# Compute_Module_EXT_INTERFACES.net
KiCad netlist of a schematic drawn in Altium Designer
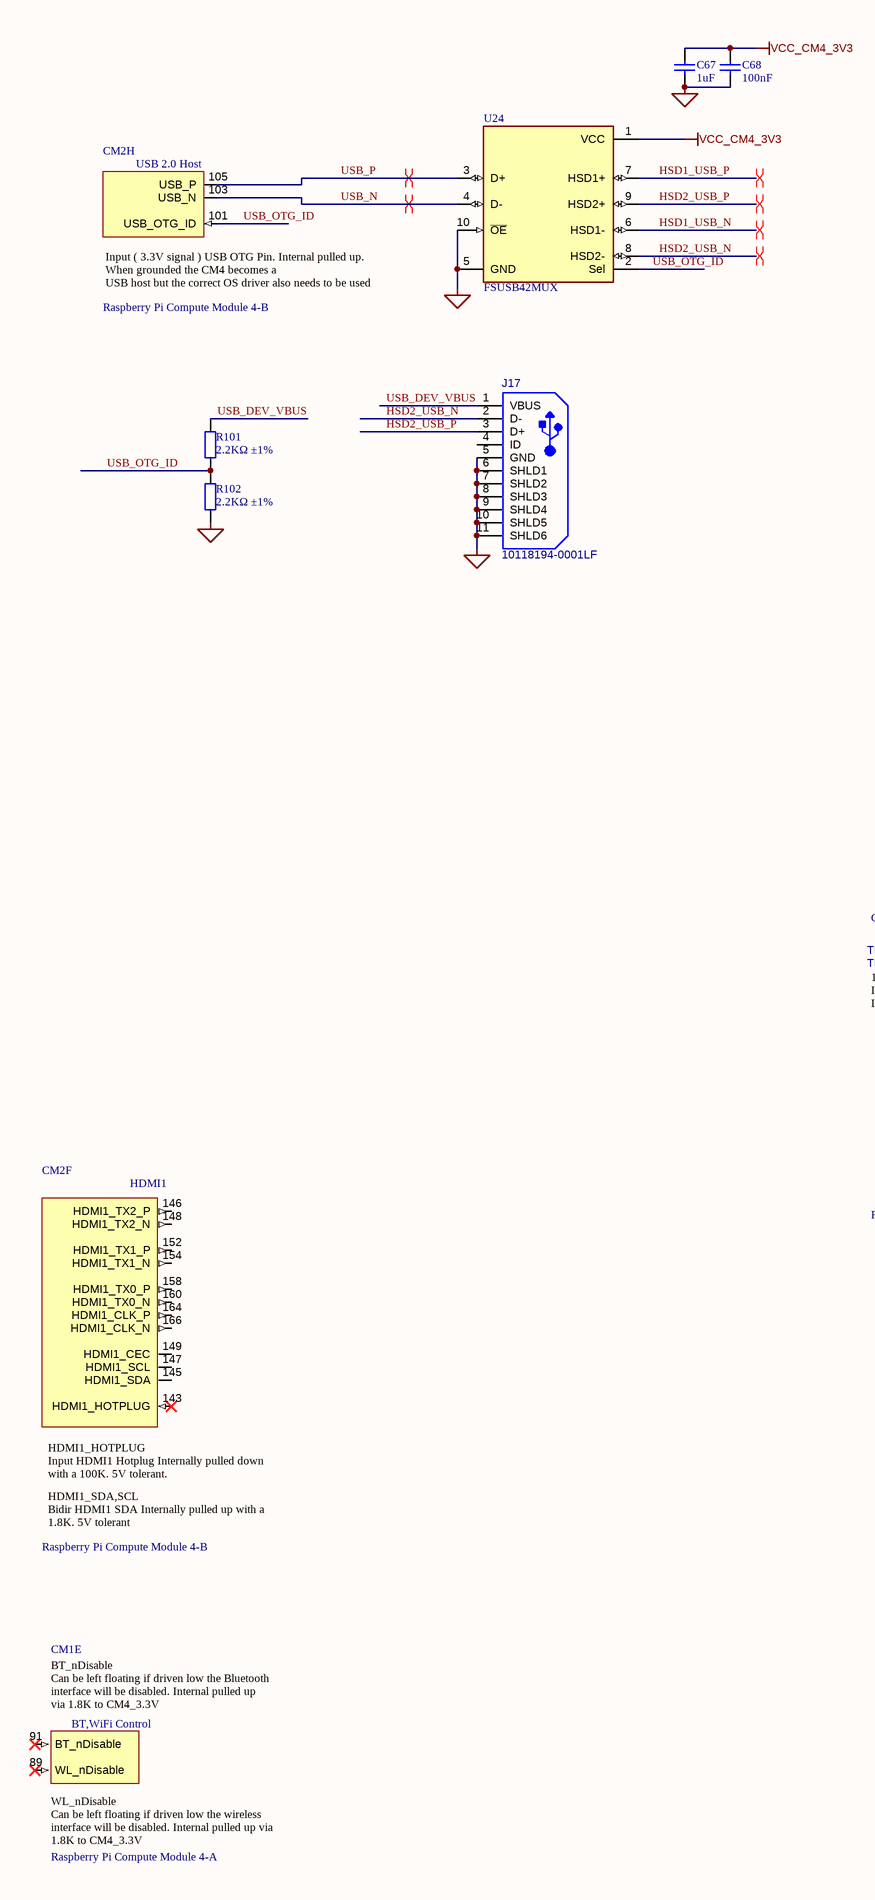
[diagram p0: Compute_Module_EXT_INTERFACES.SchDoc, left]
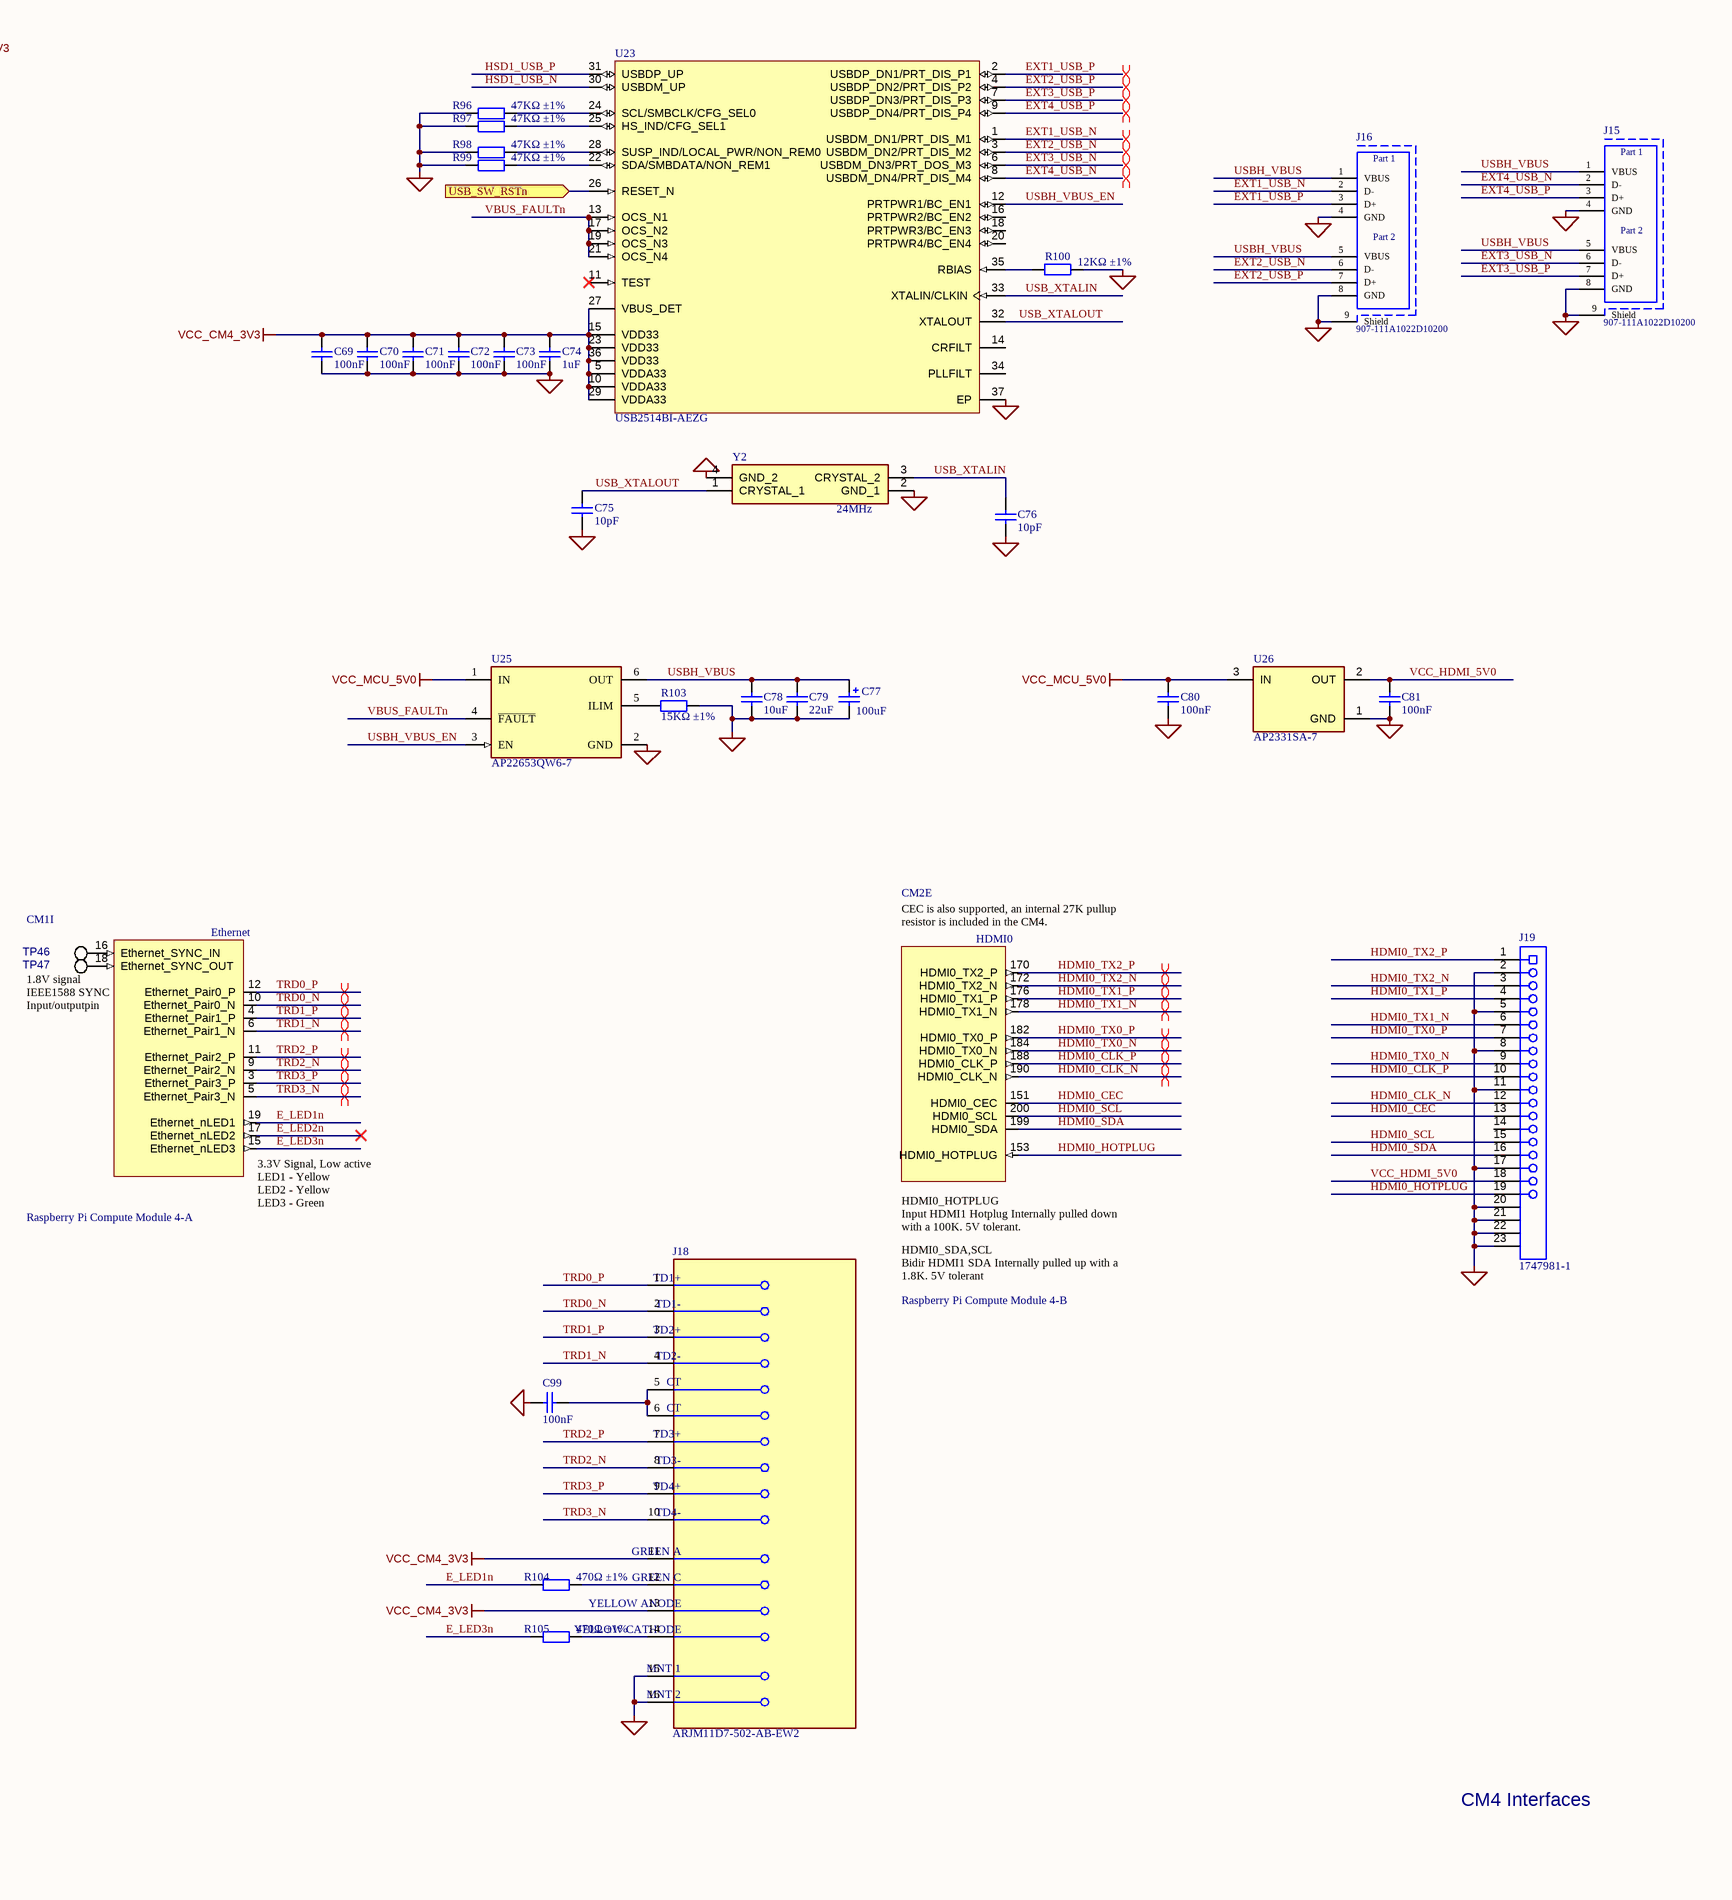
[diagram p1: Compute_Module_EXT_INTERFACES.SchDoc, right]

(export (version "E")
  (design (tool "Eeschema 10.0.6"))
  (components
    (comp (ref "C67")
      (value "1uF")
      (footprint "0603_C")
      (description "Chip capacitors")
      (fields
        (field (name "MANUFACTURER") "Samsung Electro-Mechanics")
        (field (name "MANUFACTURER PART NUMBER") "CL10A105KB8NNNC")
      )
      (libsource (lib "Cap") (part "0603 1uF (105) 10% 50V"))
    )
    (comp (ref "C68")
      (value "100nF")
      (footprint "0603_C")
      (description "Chip capacitors")
      (fields
        (field (name "MANUFACTURER") "YAGEO")
        (field (name "MANUFACTURER PART NUMBER") "CC0603KRX7R9BB104")
      )
      (libsource (lib "Cap") (part "0603 100nF (104) 10% 50V"))
    )
    (comp (ref "C69")
      (value "100nF")
      (footprint "0603_C")
      (description "Chip capacitors")
      (fields
        (field (name "MANUFACTURER") "YAGEO")
        (field (name "MANUFACTURER PART NUMBER") "CC0603KRX7R9BB104")
      )
      (libsource (lib "Cap") (part "0603 100nF (104) 10% 50V"))
    )
    (comp (ref "C70")
      (value "100nF")
      (footprint "0603_C")
      (description "Chip capacitors")
      (fields
        (field (name "MANUFACTURER") "YAGEO")
        (field (name "MANUFACTURER PART NUMBER") "CC0603KRX7R9BB104")
      )
      (libsource (lib "Cap") (part "0603 100nF (104) 10% 50V"))
    )
    (comp (ref "C71")
      (value "100nF")
      (footprint "0603_C")
      (description "Chip capacitors")
      (fields
        (field (name "MANUFACTURER") "YAGEO")
        (field (name "MANUFACTURER PART NUMBER") "CC0603KRX7R9BB104")
      )
      (libsource (lib "Cap") (part "0603 100nF (104) 10% 50V"))
    )
    (comp (ref "C72")
      (value "100nF")
      (footprint "0603_C")
      (description "Chip capacitors")
      (fields
        (field (name "MANUFACTURER") "YAGEO")
        (field (name "MANUFACTURER PART NUMBER") "CC0603KRX7R9BB104")
      )
      (libsource (lib "Cap") (part "0603 100nF (104) 10% 50V"))
    )
    (comp (ref "C73")
      (value "100nF")
      (footprint "0603_C")
      (description "Chip capacitors")
      (fields
        (field (name "MANUFACTURER") "YAGEO")
        (field (name "MANUFACTURER PART NUMBER") "CC0603KRX7R9BB104")
      )
      (libsource (lib "Cap") (part "0603 100nF (104) 10% 50V"))
    )
    (comp (ref "C74")
      (value "1uF")
      (footprint "0603_C")
      (description "Chip capacitors")
      (fields
        (field (name "MANUFACTURER") "Samsung Electro-Mechanics")
        (field (name "MANUFACTURER PART NUMBER") "CL10A105KB8NNNC")
      )
      (libsource (lib "Cap") (part "0603 1uF (105) 10% 50V"))
    )
    (comp (ref "C75")
      (value "10pF")
      (footprint "0603_C")
      (description "Chip capacitors")
      (fields
        (field (name "MANUFACTURER") "Samsung Electro-Mechanics")
        (field (name "PARTNUMBER") "CL10C100JB8NNNC")
      )
      (libsource (lib "Cap") (part "0603 10pF (100) 5% 50V"))
    )
    (comp (ref "C76")
      (value "10pF")
      (footprint "0603_C")
      (description "Chip capacitors")
      (fields
        (field (name "MANUFACTURER") "Samsung Electro-Mechanics")
        (field (name "PARTNUMBER") "CL10C100JB8NNNC")
      )
      (libsource (lib "Cap") (part "0603 10pF (100) 5% 50V"))
    )
    (comp (ref "C77")
      (value "100uF")
      (footprint "WCAP-ASLI_D6.3H7.7")
      (fields
        (field (name "MANUFACTURER") "Capxon International Elec")
        (field (name "MANUFACTURER PART NUMBER") "HV101M035E077ETR")
      )
      (libsource (lib "IQAnalog") (part "865080445010"))
    )
    (comp (ref "C78")
      (value "10uF")
      (footprint "1206_C")
      (description "Chip capacitors")
      (fields
        (field (name "MANUFACTURER") "Samsung Electro-Mechanics")
        (field (name "MANUFACTURER PART NUMBER") "CL31A106KBHNNNE")
      )
      (libsource (lib "Cap") (part "1206 10uF (106) 10% 50V"))
    )
    (comp (ref "C79")
      (value "22uF")
      (footprint "0805_C")
      (description "Chip capacitors")
      (fields
        (field (name "MANUFACTURER") "Samsung Electro-Mechanics")
        (field (name "PARTNUMBER") "CL21A226MAQNNNE")
      )
      (libsource (lib "Cap") (part "0805 22uF (226) 20% 25V"))
    )
    (comp (ref "C80")
      (value "100nF")
      (footprint "0603_C")
      (description "Chip capacitors")
      (fields
        (field (name "MANUFACTURER") "YAGEO")
        (field (name "MANUFACTURER PART NUMBER") "CC0603KRX7R9BB104")
      )
      (libsource (lib "Cap") (part "0603 100nF (104) 10% 50V"))
    )
    (comp (ref "C81")
      (value "100nF")
      (footprint "0603_C")
      (description "Chip capacitors")
      (fields
        (field (name "MANUFACTURER") "YAGEO")
        (field (name "MANUFACTURER PART NUMBER") "CC0603KRX7R9BB104")
      )
      (libsource (lib "Cap") (part "0603 100nF (104) 10% 50V"))
    )
    (comp (ref "C99")
      (value "100nF")
      (footprint "0603_C")
      (description "Chip capacitors")
      (fields
        (field (name "MANUFACTURER") "YAGEO")
        (field (name "MANUFACTURER PART NUMBER") "CC0603KRX7R9BB104")
      )
      (libsource (lib "Cap") (part "0603 100nF (104) 10% 50V"))
    )
    (comp (ref "CM1")
      (value "Raspberry Pi Compute Module 4-A")
      (footprint "DF40HC30100DS04V51")
      (description "Raspberry Pi Compute Module 4 Pins 1-100 (Connector A)")
      (fields
        (field (name "MANUFACTURER") "Hirose")
        (field (name "MANUFACTURER PART NUMBER") "DF40HC(3.0)-100DS-0.4V(51)")
      )
      (libsource (lib "Sienci_Labs") (part "CM4_Module_A"))
    )
    (comp (ref "CM2")
      (value "Raspberry Pi Compute Module 4-B")
      (footprint "DF40HC30100DS04V51 - p101-200")
      (description "Raspberry Pi Compute Module 4 Pins 101-200 (Connector B)")
      (fields
        (field (name "MANUFACTURER") "Hirose")
        (field (name "MANUFACTURER PART NUMBER") "DF40HC(3.0)-100DS-0.4V(51)")
      )
      (libsource (lib "Sienci_Labs") (part "CM4_Module_B"))
    )
    (comp (ref "J15")
      (value "907-111A1022D10200")
      (footprint "USB-A-TH_USB-M-51")
      (description "USB 2.0 2 8 Female Type-A Plugin USB Connectors ROHS")
      (fields (field (name "MANUFACTURER") "Jing Extension of the Electronic Co."))
      (libsource (lib "Sienci_Labs") (part "907-111A1022D10200"))
    )
    (comp (ref "J16")
      (value "907-111A1022D10200")
      (footprint "USB-A-TH_USB-M-51")
      (description "USB 2.0 2 8 Female Type-A Plugin USB Connectors ROHS")
      (fields (field (name "MANUFACTURER") "Jing Extension of the Electronic Co."))
      (libsource (lib "Sienci_Labs") (part "907-111A1022D10200"))
    )
    (comp (ref "J17")
      (value "10118194-0001LF")
      (footprint "FCI-10118194-0001LF-5_V")
      (description "CONN RCPT USB2.0 MICRO B SMD R/A")
      (fields (field (name "MANUFACTURER") "Amphenol ICC (FCI)"))
      (libsource (lib "Sienci_Labs") (part "USB-5-6SHLD"))
    )
    (comp (ref "J18")
      (value "ARJM11D7-502-AB-EW2")
      (footprint "FP-ARJM11D7-502-AB-EW2-MFG")
      (description "1 Port RJ45Through Hole 10/100/1000 Base-T, AutoMDIX")
      (fields (field (name "MANUFACTURER") "Abracon LLC"))
      (libsource (lib "Sienci_Labs") (part "ARJM11D7-502-AB-EW2"))
    )
    (comp (ref "J19")
      (value "1747981-1")
      (footprint "TE-1747981-1_V")
      (description "HDMI Receptacle, Pitch 0.5 mm, 19 Position, Height 6.38 mm, RoHS, Tape and Reel")
      (fields (field (name "TOLERANCE") "1%") (field (name "MANUFACTURER") "TE Connectivity"))
      (libsource (lib "Altium Content Vault") (part "CN-1P-F-HD19"))
    )
    (comp (ref "R96")
      (value "47KΩ ±1%")
      (footprint "0402_R")
      (description "Chip resistor")
      (fields (field (name "MANUFACTURER") "Uniroyal Elec") (field (name "PARTNUMBER") "0402WGF4702TCE"))
      (libsource (lib "RES") (part "0402 47K (4702) 1%"))
    )
    (comp (ref "R97")
      (value "47KΩ ±1%")
      (footprint "0402_R")
      (description "Chip resistor")
      (fields (field (name "MANUFACTURER") "Uniroyal Elec") (field (name "PARTNUMBER") "0402WGF4702TCE"))
      (libsource (lib "RES") (part "0402 47K (4702) 1%"))
    )
    (comp (ref "R98")
      (value "47KΩ ±1%")
      (footprint "0402_R")
      (description "Chip resistor")
      (fields (field (name "MANUFACTURER") "Uniroyal Elec") (field (name "PARTNUMBER") "0402WGF4702TCE"))
      (libsource (lib "RES") (part "0402 47K (4702) 1%"))
    )
    (comp (ref "R99")
      (value "47KΩ ±1%")
      (footprint "0402_R")
      (description "Chip resistor")
      (fields (field (name "MANUFACTURER") "Uniroyal Elec") (field (name "PARTNUMBER") "0402WGF4702TCE"))
      (libsource (lib "RES") (part "0402 47K (4702) 1%"))
    )
    (comp (ref "R100")
      (value "12KΩ ±1%")
      (footprint "0402_R")
      (description "Chip resistor")
      (fields (field (name "MANUFACTURER") "Uniroyal Elec") (field (name "PARTNUMBER") "0402WGF1202TCE"))
      (libsource (lib "RES") (part "0402 12K (1202) 1%"))
    )
    (comp (ref "R101")
      (value "2.2KΩ ±1%")
      (footprint "0402_R")
      (description "Chip resistor")
      (fields (field (name "MANUFACTURER") "Uniroyal Elec") (field (name "PARTNUMBER") "0402WGF2201TCE"))
      (libsource (lib "RES") (part "0402 2.2K (2201) 1%"))
    )
    (comp (ref "R102")
      (value "2.2KΩ ±1%")
      (footprint "0402_R")
      (description "Chip resistor")
      (fields (field (name "MANUFACTURER") "Uniroyal Elec") (field (name "PARTNUMBER") "0402WGF2201TCE"))
      (libsource (lib "RES") (part "0402 2.2K (2201) 1%"))
    )
    (comp (ref "R103")
      (value "15KΩ ±1%")
      (footprint "0402_R")
      (description "Chip resistor")
      (fields (field (name "MANUFACTURER") "Uniroyal Elec") (field (name "PARTNUMBER") "0402WGF1502TCE"))
      (libsource (lib "RES") (part "0402 15K (1502) 1%"))
    )
    (comp (ref "R104")
      (value "470Ω ±1%")
      (footprint "0402_R")
      (description "Chip resistor")
      (fields (field (name "MANUFACTURER") "Uniroyal Elec") (field (name "PARTNUMBER") "0402WGF4700TCE"))
      (libsource (lib "RES") (part "0402 470R (4700) 1%"))
    )
    (comp (ref "R105")
      (value "470Ω ±1%")
      (footprint "0402_R")
      (description "Chip resistor")
      (fields (field (name "MANUFACTURER") "Uniroyal Elec") (field (name "PARTNUMBER") "0402WGF4700TCE"))
      (libsource (lib "RES") (part "0402 470R (4700) 1%"))
    )
    (comp (ref "TP46")
      (value "TESTPOINT")
      (footprint "TP/SMALL")
      (description "Test Point")
      (libsource (lib "Sienci_Labs") (part "TESTPOINT"))
    )
    (comp (ref "TP47")
      (value "TESTPOINT")
      (footprint "TP/SMALL")
      (description "Test Point")
      (libsource (lib "Sienci_Labs") (part "TESTPOINT"))
    )
    (comp (ref "U23")
      (value "USB2514BI-AEZG")
      (footprint "QFN50P600X600X100-37N-D")
      (description "Microchip USB2514BI-AEZG; USB Controller; 480Mbit/s; USB 2.0; 3.3 V; 36-Pin QFN")
      (fields (field (name "MANUFACTURER") "Microchip"))
      (libsource (lib "Sienci_Labs") (part "USB2514BI-AEZG"))
    )
    (comp (ref "U24")
      (value "FSUSB42MUX")
      (footprint "SOP50P490X110-10N")
      (description "FSUSB42 Series DPDT 4.3 V 480 Mbps SMT Hi Speed USB 2.0 Switch - MSOP-10")
      (fields (field (name "VOLTAGE") "4.3V") (field (name "MANUFACTURER") "ON Semiconductor / Fairchild"))
      (libsource (lib "Sienci_Labs") (part "FSUSB42MUX"))
    )
    (comp (ref "U25")
      (value "AP22653QW6-7")
      (footprint "SOT95P280X145-6N")
      (description "ESDA Series 14.2 V 90 pF Automotive Dual Transil ESD Array - SOT-23")
      (fields (field (name "MANUFACTURER") "Diodes"))
      (libsource (lib "Sienci_Labs") (part "AP22653QW6-7"))
    )
    (comp (ref "U26")
      (value "AP2331SA-7")
      (footprint "SOT91P240X120-3N")
      (description "AP2331 Series Single Channel 0.2 A Current-Limited Load Switch - SOT-23")
      (fields (field (name "MANUFACTURER") "Diodes"))
      (libsource (lib "Sienci_Labs") (part "AP2331SA-7"))
    )
    (comp (ref "Y2")
      (value "24MHz")
      (footprint "YSX321SL")
      (description "24MHz SMD Crystal Resonator 20pF 60Ω ±10ppm -40℃~+85℃ SMD3225-4P Crystals ROHS")
      (fields (field (name "MANUFACTURER_PART_NUMBER") "S3224000201060") (field (name "MANUFACTURER") "JGHC"))
      (libsource (lib "Sienci_Labs") (part "S3224000201060"))
    )
  )
  (nets
    (net (code "1") (name "/EXT1_USB_N") (class "Default")
      (node (ref "J16") (pin "2") (pinfunction "D-_2") (pintype "passive"))
      (node (ref "U23") (pin "1") (pinfunction "USBDM_DN1/PRT_DIS_M1_1") (pintype "bidirectional"))
    )
    (net (code "2") (name "/EXT1_USB_P") (class "Default")
      (node (ref "J16") (pin "3") (pinfunction "D+_3") (pintype "passive"))
      (node (ref "U23") (pin "2") (pinfunction "USBDP_DN1/PRT_DIS_P1_2") (pintype "bidirectional"))
    )
    (net (code "3") (name "/EXT2_USB_N") (class "Default")
      (node (ref "J16") (pin "6") (pinfunction "D-_6") (pintype "passive"))
      (node (ref "U23") (pin "3") (pinfunction "USBDM_DN2/PRT_DIS_M2_3") (pintype "bidirectional"))
    )
    (net (code "4") (name "/EXT2_USB_P") (class "Default")
      (node (ref "J16") (pin "7") (pinfunction "D+_7") (pintype "passive"))
      (node (ref "U23") (pin "4") (pinfunction "USBDP_DN2/PRT_DIS_P2_4") (pintype "bidirectional"))
    )
    (net (code "5") (name "/EXT3_USB_N") (class "Default")
      (node (ref "J15") (pin "6") (pinfunction "D-_6") (pintype "passive"))
      (node (ref "U23") (pin "6") (pinfunction "USBDM_DN3/PRT_DOS_M3_6") (pintype "bidirectional"))
    )
    (net (code "6") (name "/EXT3_USB_P") (class "Default")
      (node (ref "J15") (pin "7") (pinfunction "D+_7") (pintype "passive"))
      (node (ref "U23") (pin "7") (pinfunction "USBDP_DN3/PRT_DIS_P3_7") (pintype "bidirectional"))
    )
    (net (code "7") (name "/EXT4_USB_N") (class "Default")
      (node (ref "J15") (pin "2") (pinfunction "D-_2") (pintype "passive"))
      (node (ref "U23") (pin "8") (pinfunction "USBDM_DN4/PRT_DIS_M4_8") (pintype "bidirectional"))
    )
    (net (code "8") (name "/EXT4_USB_P") (class "Default")
      (node (ref "J15") (pin "3") (pinfunction "D+_3") (pintype "passive"))
      (node (ref "U23") (pin "9") (pinfunction "USBDP_DN4/PRT_DIS_P4_9") (pintype "bidirectional"))
    )
    (net (code "9") (name "/E_LED1n") (class "Default")
      (node (ref "CM1") (pin "19") (pinfunction "Ethernet_nLED1_19") (pintype "output"))
      (node (ref "R104") (pin "1") (pinfunction "1_1") (pintype "passive"))
    )
    (net (code "10") (name "/E_LED2n") (class "Default")
      (node (ref "CM1") (pin "17") (pinfunction "Ethernet_nLED2_17") (pintype "output+no_connect"))
    )
    (net (code "11") (name "/E_LED3n") (class "Default")
      (node (ref "CM1") (pin "15") (pinfunction "Ethernet_nLED3_15") (pintype "output"))
      (node (ref "R105") (pin "1") (pinfunction "1_1") (pintype "passive"))
    )
    (net (code "12") (name "/HDMI0_CEC") (class "Default")
      (node (ref "CM2") (pin "151") (pinfunction "HDMI0_CEC_151") (pintype "open_collector"))
      (node (ref "J19") (pin "13") (pinfunction "13_13") (pintype "passive"))
    )
    (net (code "13") (name "/HDMI0_CLK_N") (class "Default")
      (node (ref "CM2") (pin "190") (pinfunction "HDMI0_CLK_N_190") (pintype "output"))
      (node (ref "J19") (pin "12") (pinfunction "12_12") (pintype "passive"))
    )
    (net (code "14") (name "/HDMI0_CLK_P") (class "Default")
      (node (ref "CM2") (pin "188") (pinfunction "HDMI0_CLK_P_188") (pintype "output"))
      (node (ref "J19") (pin "10") (pinfunction "10_10") (pintype "passive"))
    )
    (net (code "15") (name "/HDMI0_HOTPLUG") (class "Default")
      (node (ref "CM2") (pin "153") (pinfunction "HDMI0_HOTPLUG_153") (pintype "input"))
      (node (ref "J19") (pin "19") (pinfunction "19_19") (pintype "passive"))
    )
    (net (code "16") (name "/HDMI0_SCL") (class "Default")
      (node (ref "CM2") (pin "200") (pinfunction "HDMI0_SCL_200") (pintype "open_collector"))
      (node (ref "J19") (pin "15") (pinfunction "15_15") (pintype "passive"))
    )
    (net (code "17") (name "/HDMI0_SDA") (class "Default")
      (node (ref "CM2") (pin "199") (pinfunction "HDMI0_SDA_199") (pintype "bidirectional"))
      (node (ref "J19") (pin "16") (pinfunction "16_16") (pintype "passive"))
    )
    (net (code "18") (name "/HDMI0_TX0_N") (class "Default")
      (node (ref "CM2") (pin "184") (pinfunction "HDMI0_TX0_N_184") (pintype "output"))
      (node (ref "J19") (pin "9") (pinfunction "9_9") (pintype "passive"))
    )
    (net (code "19") (name "/HDMI0_TX0_P") (class "Default")
      (node (ref "CM2") (pin "182") (pinfunction "HDMI0_TX0_P_182") (pintype "output"))
      (node (ref "J19") (pin "7") (pinfunction "7_7") (pintype "passive"))
    )
    (net (code "20") (name "/HDMI0_TX1_N") (class "Default")
      (node (ref "CM2") (pin "178") (pinfunction "HDMI0_TX1_N_178") (pintype "output"))
      (node (ref "J19") (pin "6") (pinfunction "6_6") (pintype "passive"))
    )
    (net (code "21") (name "/HDMI0_TX1_P") (class "Default")
      (node (ref "CM2") (pin "176") (pinfunction "HDMI0_TX1_P_176") (pintype "output"))
      (node (ref "J19") (pin "4") (pinfunction "4_4") (pintype "passive"))
    )
    (net (code "22") (name "/HDMI0_TX2_N") (class "Default")
      (node (ref "CM2") (pin "172") (pinfunction "HDMI0_TX2_N_172") (pintype "output"))
      (node (ref "J19") (pin "3") (pinfunction "3_3") (pintype "passive"))
    )
    (net (code "23") (name "/HDMI0_TX2_P") (class "Default")
      (node (ref "CM2") (pin "170") (pinfunction "HDMI0_TX2_P_170") (pintype "output"))
      (node (ref "J19") (pin "1") (pinfunction "1_1") (pintype "passive"))
    )
    (net (code "24") (name "/HSD1_USB_N") (class "Default")
      (node (ref "U23") (pin "30") (pinfunction "USBDM_UP_30") (pintype "bidirectional"))
      (node (ref "U24") (pin "6") (pinfunction "HSD1-_6") (pintype "bidirectional"))
    )
    (net (code "25") (name "/HSD1_USB_P") (class "Default")
      (node (ref "U23") (pin "31") (pinfunction "USBDP_UP_31") (pintype "bidirectional"))
      (node (ref "U24") (pin "7") (pinfunction "HSD1+_7") (pintype "bidirectional"))
    )
    (net (code "26") (name "/HSD2_USB_N") (class "Default")
      (node (ref "J17") (pin "2") (pinfunction "D-_2") (pintype "passive"))
      (node (ref "U24") (pin "8") (pinfunction "HSD2-_8") (pintype "bidirectional"))
    )
    (net (code "27") (name "/HSD2_USB_P") (class "Default")
      (node (ref "J17") (pin "3") (pinfunction "D+_3") (pintype "passive"))
      (node (ref "U24") (pin "9") (pinfunction "HSD2+_9") (pintype "bidirectional"))
    )
    (net (code "28") (name "/TRD0_N") (class "Default")
      (node (ref "CM1") (pin "10") (pinfunction "Ethernet_Pair0_N_10") (pintype "passive"))
      (node (ref "J18") (pin "2") (pinfunction "TD1-_2") (pintype "passive"))
    )
    (net (code "29") (name "/TRD0_P") (class "Default")
      (node (ref "CM1") (pin "12") (pinfunction "Ethernet_Pair0_P_12") (pintype "passive"))
      (node (ref "J18") (pin "1") (pinfunction "TD1+_1") (pintype "passive"))
    )
    (net (code "30") (name "/TRD1_N") (class "Default")
      (node (ref "CM1") (pin "6") (pinfunction "Ethernet_Pair1_N_6") (pintype "passive"))
      (node (ref "J18") (pin "4") (pinfunction "TD2-_4") (pintype "passive"))
    )
    (net (code "31") (name "/TRD1_P") (class "Default")
      (node (ref "CM1") (pin "4") (pinfunction "Ethernet_Pair1_P_4") (pintype "passive"))
      (node (ref "J18") (pin "3") (pinfunction "TD2+_3") (pintype "passive"))
    )
    (net (code "32") (name "/TRD2_N") (class "Default")
      (node (ref "CM1") (pin "9") (pinfunction "Ethernet_Pair2_N_9") (pintype "passive"))
      (node (ref "J18") (pin "8") (pinfunction "TD3-_8") (pintype "passive"))
    )
    (net (code "33") (name "/TRD2_P") (class "Default")
      (node (ref "CM1") (pin "11") (pinfunction "Ethernet_Pair2_P_11") (pintype "passive"))
      (node (ref "J18") (pin "7") (pinfunction "TD3+_7") (pintype "passive"))
    )
    (net (code "34") (name "/TRD3_N") (class "Default")
      (node (ref "CM1") (pin "5") (pinfunction "Ethernet_Pair3_N_5") (pintype "passive"))
      (node (ref "J18") (pin "10") (pinfunction "TD4-_10") (pintype "passive"))
    )
    (net (code "35") (name "/TRD3_P") (class "Default")
      (node (ref "CM1") (pin "3") (pinfunction "Ethernet_Pair3_P_3") (pintype "passive"))
      (node (ref "J18") (pin "9") (pinfunction "TD4+_9") (pintype "passive"))
    )
    (net (code "36") (name "/USBH_VBUS") (class "Default")
      (node (ref "C77") (pin "1") (pinfunction "P_1") (pintype "passive"))
      (node (ref "C78") (pin "2") (pinfunction "2_2") (pintype "passive"))
      (node (ref "C79") (pin "2") (pinfunction "2_2") (pintype "passive"))
      (node (ref "J15") (pin "1") (pinfunction "VBUS_1") (pintype "passive"))
      (node (ref "J15") (pin "5") (pinfunction "VBUS_5") (pintype "passive"))
      (node (ref "J16") (pin "1") (pinfunction "VBUS_1") (pintype "passive"))
      (node (ref "J16") (pin "5") (pinfunction "VBUS_5") (pintype "passive"))
      (node (ref "U25") (pin "6") (pinfunction "OUT_6") (pintype "passive"))
    )
    (net (code "37") (name "/USBH_VBUS_EN") (class "Default")
      (node (ref "U23") (pin "12") (pinfunction "PRTPWR1/BC_EN1_12") (pintype "bidirectional"))
      (node (ref "U25") (pin "3") (pinfunction "EN_3") (pintype "input"))
    )
    (net (code "38") (name "/USB_DEV_VBUS") (class "Default")
      (node (ref "J17") (pin "1") (pinfunction "VBUS_1") (pintype "passive"))
      (node (ref "R101") (pin "2") (pinfunction "2_2") (pintype "passive"))
    )
    (net (code "39") (name "/USB_N") (class "Default")
      (node (ref "CM2") (pin "103") (pinfunction "USB_N_103") (pintype "passive"))
      (node (ref "U24") (pin "4") (pinfunction "D-_4") (pintype "bidirectional"))
    )
    (net (code "40") (name "/USB_OTG_ID") (class "Default")
      (node (ref "CM2") (pin "101") (pinfunction "USB_OTG_ID_101") (pintype "input"))
      (node (ref "R101") (pin "1") (pinfunction "1_1") (pintype "passive"))
      (node (ref "R102") (pin "2") (pinfunction "2_2") (pintype "passive"))
      (node (ref "U24") (pin "2") (pinfunction "Sel_2") (pintype "passive"))
    )
    (net (code "41") (name "/USB_P") (class "Default")
      (node (ref "CM2") (pin "105") (pinfunction "USB_P_105") (pintype "passive"))
      (node (ref "U24") (pin "3") (pinfunction "D+_3") (pintype "bidirectional"))
    )
    (net (code "42") (name "/USB_SW_RSTn") (class "Default")
      (node (ref "U23") (pin "26") (pinfunction "RESET_N_26") (pintype "input"))
    )
    (net (code "43") (name "/USB_XTALIN") (class "Default")
      (node (ref "C76") (pin "2") (pinfunction "2_2") (pintype "passive"))
      (node (ref "U23") (pin "33") (pinfunction "XTALIN/CLKIN_33") (pintype "input"))
      (node (ref "Y2") (pin "3") (pinfunction "CRYSTAL_2_3") (pintype "passive"))
    )
    (net (code "44") (name "/USB_XTALOUT") (class "Default")
      (node (ref "C75") (pin "2") (pinfunction "2_2") (pintype "passive"))
      (node (ref "U23") (pin "32") (pinfunction "XTALOUT_32") (pintype "passive"))
      (node (ref "Y2") (pin "1") (pinfunction "CRYSTAL_1_1") (pintype "passive"))
    )
    (net (code "45") (name "/VBUS_FAULTn") (class "Default")
      (node (ref "U23") (pin "13") (pinfunction "OCS_N1_13") (pintype "input"))
      (node (ref "U23") (pin "17") (pinfunction "OCS_N2_17") (pintype "input"))
      (node (ref "U23") (pin "19") (pinfunction "OCS_N3_19") (pintype "input"))
      (node (ref "U23") (pin "21") (pinfunction "OCS_N4_21") (pintype "input"))
      (node (ref "U25") (pin "4") (pinfunction "~{FAULT}_4") (pintype "open_collector"))
    )
    (net (code "46") (name "/VCC_HDMI_5V0") (class "Default")
      (node (ref "C81") (pin "2") (pinfunction "2_2") (pintype "passive"))
      (node (ref "J19") (pin "18") (pinfunction "18_18") (pintype "passive"))
      (node (ref "U26") (pin "2") (pinfunction "OUT_2") (pintype "power_in"))
    )
    (net (code "47") (name "MCU_GND") (class "Default")
      (node (ref "C67") (pin "1") (pinfunction "1_1") (pintype "passive"))
      (node (ref "C68") (pin "1") (pinfunction "1_1") (pintype "passive"))
      (node (ref "C69") (pin "1") (pinfunction "1_1") (pintype "passive"))
      (node (ref "C70") (pin "1") (pinfunction "1_1") (pintype "passive"))
      (node (ref "C71") (pin "1") (pinfunction "1_1") (pintype "passive"))
      (node (ref "C72") (pin "1") (pinfunction "1_1") (pintype "passive"))
      (node (ref "C73") (pin "1") (pinfunction "1_1") (pintype "passive"))
      (node (ref "C74") (pin "1") (pinfunction "1_1") (pintype "passive"))
      (node (ref "C75") (pin "1") (pinfunction "1_1") (pintype "passive"))
      (node (ref "C76") (pin "1") (pinfunction "1_1") (pintype "passive"))
      (node (ref "C77") (pin "2") (pinfunction "N_2") (pintype "passive"))
      (node (ref "C78") (pin "1") (pinfunction "1_1") (pintype "passive"))
      (node (ref "C79") (pin "1") (pinfunction "1_1") (pintype "passive"))
      (node (ref "C80") (pin "1") (pinfunction "1_1") (pintype "passive"))
      (node (ref "C81") (pin "1") (pinfunction "1_1") (pintype "passive"))
      (node (ref "C99") (pin "2") (pinfunction "2_2") (pintype "passive"))
      (node (ref "J15") (pin "4") (pinfunction "GND_4") (pintype "passive"))
      (node (ref "J15") (pin "8") (pinfunction "GND_8") (pintype "passive"))
      (node (ref "J15") (pin "9") (pinfunction "Shield_9") (pintype "passive"))
      (node (ref "J16") (pin "4") (pinfunction "GND_4") (pintype "passive"))
      (node (ref "J16") (pin "8") (pinfunction "GND_8") (pintype "passive"))
      (node (ref "J16") (pin "9") (pinfunction "Shield_9") (pintype "passive"))
      (node (ref "J17") (pin "10") (pinfunction "SHLD5_10") (pintype "passive"))
      (node (ref "J17") (pin "11") (pinfunction "SHLD6_11") (pintype "passive"))
      (node (ref "J17") (pin "5") (pinfunction "GND_5") (pintype "passive"))
      (node (ref "J17") (pin "6") (pinfunction "SHLD1_6") (pintype "passive"))
      (node (ref "J17") (pin "7") (pinfunction "SHLD2_7") (pintype "passive"))
      (node (ref "J17") (pin "8") (pinfunction "SHLD3_8") (pintype "passive"))
      (node (ref "J17") (pin "9") (pinfunction "SHLD4_9") (pintype "passive"))
      (node (ref "J18") (pin "15") (pinfunction "MNT_1_15") (pintype "passive"))
      (node (ref "J18") (pin "16") (pinfunction "MNT_2_16") (pintype "passive"))
      (node (ref "J19") (pin "11") (pinfunction "11_11") (pintype "passive"))
      (node (ref "J19") (pin "17") (pinfunction "17_17") (pintype "passive"))
      (node (ref "J19") (pin "2") (pinfunction "2_2") (pintype "passive"))
      (node (ref "J19") (pin "20") (pinfunction "SHLD1_20") (pintype "passive"))
      (node (ref "J19") (pin "21") (pinfunction "SHLD2_21") (pintype "passive"))
      (node (ref "J19") (pin "22") (pinfunction "SHLD3_22") (pintype "passive"))
      (node (ref "J19") (pin "23") (pinfunction "SHLD4_23") (pintype "passive"))
      (node (ref "J19") (pin "5") (pinfunction "5_5") (pintype "passive"))
      (node (ref "J19") (pin "8") (pinfunction "8_8") (pintype "passive"))
      (node (ref "R100") (pin "2") (pinfunction "2_2") (pintype "passive"))
      (node (ref "R102") (pin "1") (pinfunction "1_1") (pintype "passive"))
      (node (ref "R103") (pin "2") (pinfunction "2_2") (pintype "passive"))
      (node (ref "R96") (pin "2") (pinfunction "2_2") (pintype "passive"))
      (node (ref "R97") (pin "2") (pinfunction "2_2") (pintype "passive"))
      (node (ref "R98") (pin "2") (pinfunction "2_2") (pintype "passive"))
      (node (ref "R99") (pin "2") (pinfunction "2_2") (pintype "passive"))
      (node (ref "U23") (pin "37") (pinfunction "EP_37") (pintype "power_in"))
      (node (ref "U24") (pin "10") (pinfunction "~{OE}_10") (pintype "input"))
      (node (ref "U24") (pin "5") (pinfunction "GND_5") (pintype "power_in"))
      (node (ref "U25") (pin "2") (pinfunction "GND_2") (pintype "power_in"))
      (node (ref "U26") (pin "1") (pinfunction "GND_1") (pintype "power_in"))
      (node (ref "Y2") (pin "2") (pinfunction "GND_1_2") (pintype "passive"))
      (node (ref "Y2") (pin "4") (pinfunction "GND_2_4") (pintype "passive"))
    )
    (net (code "48") (name "Net-(C99-Pad1)") (class "Default")
      (node (ref "C99") (pin "1") (pinfunction "1_1") (pintype "passive"))
      (node (ref "J18") (pin "5") (pinfunction "CT_5") (pintype "passive"))
      (node (ref "J18") (pin "6") (pinfunction "CT_6") (pintype "passive"))
    )
    (net (code "49") (name "Net-(CM1I-Ethernet_SYNC_IN)") (class "Default")
      (node (ref "CM1") (pin "16") (pinfunction "Ethernet_SYNC_IN_16") (pintype "input"))
      (node (ref "TP46") (pin "1") (pintype "passive"))
    )
    (net (code "50") (name "Net-(CM1I-Ethernet_SYNC_OUT)") (class "Default")
      (node (ref "CM1") (pin "18") (pinfunction "Ethernet_SYNC_OUT_18") (pintype "input"))
      (node (ref "TP47") (pin "1") (pintype "passive"))
    )
    (net (code "51") (name "Net-(J18-GREEN_C)") (class "Default")
      (node (ref "J18") (pin "12") (pinfunction "GREEN_C_12") (pintype "passive"))
      (node (ref "R104") (pin "2") (pinfunction "2_2") (pintype "passive"))
    )
    (net (code "52") (name "Net-(J18-YELLOW_CATHODE)") (class "Default")
      (node (ref "J18") (pin "14") (pinfunction "YELLOW_CATHODE_14") (pintype "passive"))
      (node (ref "R105") (pin "2") (pinfunction "2_2") (pintype "passive"))
    )
    (net (code "53") (name "Net-(U23-HS_IND{slash}CFG_SEL1)") (class "Default")
      (node (ref "R97") (pin "1") (pinfunction "1_1") (pintype "passive"))
      (node (ref "U23") (pin "25") (pinfunction "HS_IND/CFG_SEL1_25") (pintype "bidirectional"))
    )
    (net (code "54") (name "Net-(U23-RBIAS)") (class "Default")
      (node (ref "R100") (pin "1") (pinfunction "1_1") (pintype "passive"))
      (node (ref "U23") (pin "35") (pinfunction "RBIAS_35") (pintype "input"))
    )
    (net (code "55") (name "Net-(U23-SCL{slash}SMBCLK{slash}CFG_SEL0)") (class "Default")
      (node (ref "R96") (pin "1") (pinfunction "1_1") (pintype "passive"))
      (node (ref "U23") (pin "24") (pinfunction "SCL/SMBCLK/CFG_SEL0_24") (pintype "bidirectional"))
    )
    (net (code "56") (name "Net-(U23-SDA{slash}SMBDATA{slash}NON_REM1)") (class "Default")
      (node (ref "R99") (pin "1") (pinfunction "1_1") (pintype "passive"))
      (node (ref "U23") (pin "22") (pinfunction "SDA/SMBDATA/NON_REM1_22") (pintype "bidirectional"))
    )
    (net (code "57") (name "Net-(U23-SUSP_IND{slash}LOCAL_PWR{slash}NON_REM0)") (class "Default")
      (node (ref "R98") (pin "1") (pinfunction "1_1") (pintype "passive"))
      (node (ref "U23") (pin "28") (pinfunction "SUSP_IND/LOCAL_PWR/NON_REM0_28") (pintype "bidirectional"))
    )
    (net (code "58") (name "Net-(U25-ILIM)") (class "Default")
      (node (ref "R103") (pin "1") (pinfunction "1_1") (pintype "passive"))
      (node (ref "U25") (pin "5") (pinfunction "ILIM_5") (pintype "passive"))
    )
    (net (code "59") (name "VCC_CM4_3V3") (class "Default")
      (node (ref "C67") (pin "2") (pinfunction "2_2") (pintype "passive"))
      (node (ref "C68") (pin "2") (pinfunction "2_2") (pintype "passive"))
      (node (ref "C69") (pin "2") (pinfunction "2_2") (pintype "passive"))
      (node (ref "C70") (pin "2") (pinfunction "2_2") (pintype "passive"))
      (node (ref "C71") (pin "2") (pinfunction "2_2") (pintype "passive"))
      (node (ref "C72") (pin "2") (pinfunction "2_2") (pintype "passive"))
      (node (ref "C73") (pin "2") (pinfunction "2_2") (pintype "passive"))
      (node (ref "C74") (pin "2") (pinfunction "2_2") (pintype "passive"))
      (node (ref "J18") (pin "11") (pinfunction "GREEN_A_11") (pintype "passive"))
      (node (ref "J18") (pin "13") (pinfunction "YELLOW_ANODE_13") (pintype "passive"))
      (node (ref "U23") (pin "10") (pinfunction "VDDA33_10") (pintype "power_in"))
      (node (ref "U23") (pin "15") (pinfunction "VDD33_15") (pintype "power_in"))
      (node (ref "U23") (pin "23") (pinfunction "VDD33_23") (pintype "power_in"))
      (node (ref "U23") (pin "27") (pinfunction "VBUS_DET_27") (pintype "power_in"))
      (node (ref "U23") (pin "29") (pinfunction "VDDA33_29") (pintype "power_in"))
      (node (ref "U23") (pin "36") (pinfunction "VDD33_36") (pintype "power_in"))
      (node (ref "U23") (pin "5") (pinfunction "VDDA33_5") (pintype "power_in"))
      (node (ref "U24") (pin "1") (pinfunction "VCC_1") (pintype "power_in"))
    )
    (net (code "60") (name "VCC_MCU_5V0") (class "Default")
      (node (ref "C80") (pin "2") (pinfunction "2_2") (pintype "passive"))
      (node (ref "U25") (pin "1") (pinfunction "IN_1") (pintype "power_in"))
      (node (ref "U26") (pin "3") (pinfunction "IN_3") (pintype "power_in"))
    )
    (net (code "61") (name "unconnected-(CM1E-BT_nDisable-Pad91)") (class "Default")
      (node (ref "CM1") (pin "91") (pinfunction "BT_nDisable_91") (pintype "input+no_connect"))
    )
    (net (code "62") (name "unconnected-(CM1E-WL_nDisable-Pad89)") (class "Default")
      (node (ref "CM1") (pin "89") (pinfunction "WL_nDisable_89") (pintype "input+no_connect"))
    )
    (net (code "63") (name "unconnected-(CM2F-HDMI1_CEC-Pad149)") (class "Default")
      (node (ref "CM2") (pin "149") (pinfunction "HDMI1_CEC_149") (pintype "open_collector"))
    )
    (net (code "64") (name "unconnected-(CM2F-HDMI1_CLK_N-Pad166)") (class "Default")
      (node (ref "CM2") (pin "166") (pinfunction "HDMI1_CLK_N_166") (pintype "output"))
    )
    (net (code "65") (name "unconnected-(CM2F-HDMI1_CLK_P-Pad164)") (class "Default")
      (node (ref "CM2") (pin "164") (pinfunction "HDMI1_CLK_P_164") (pintype "output"))
    )
    (net (code "66") (name "unconnected-(CM2F-HDMI1_HOTPLUG-Pad143)") (class "Default")
      (node (ref "CM2") (pin "143") (pinfunction "HDMI1_HOTPLUG_143") (pintype "input+no_connect"))
    )
    (net (code "67") (name "unconnected-(CM2F-HDMI1_SCL-Pad147)") (class "Default")
      (node (ref "CM2") (pin "147") (pinfunction "HDMI1_SCL_147") (pintype "open_collector"))
    )
    (net (code "68") (name "unconnected-(CM2F-HDMI1_SDA-Pad145)") (class "Default")
      (node (ref "CM2") (pin "145") (pinfunction "HDMI1_SDA_145") (pintype "bidirectional"))
    )
    (net (code "69") (name "unconnected-(CM2F-HDMI1_TX0_N-Pad160)") (class "Default")
      (node (ref "CM2") (pin "160") (pinfunction "HDMI1_TX0_N_160") (pintype "output"))
    )
    (net (code "70") (name "unconnected-(CM2F-HDMI1_TX0_P-Pad158)") (class "Default")
      (node (ref "CM2") (pin "158") (pinfunction "HDMI1_TX0_P_158") (pintype "output"))
    )
    (net (code "71") (name "unconnected-(CM2F-HDMI1_TX1_N-Pad154)") (class "Default")
      (node (ref "CM2") (pin "154") (pinfunction "HDMI1_TX1_N_154") (pintype "output"))
    )
    (net (code "72") (name "unconnected-(CM2F-HDMI1_TX1_P-Pad152)") (class "Default")
      (node (ref "CM2") (pin "152") (pinfunction "HDMI1_TX1_P_152") (pintype "output"))
    )
    (net (code "73") (name "unconnected-(CM2F-HDMI1_TX2_N-Pad148)") (class "Default")
      (node (ref "CM2") (pin "148") (pinfunction "HDMI1_TX2_N_148") (pintype "output"))
    )
    (net (code "74") (name "unconnected-(CM2F-HDMI1_TX2_P-Pad146)") (class "Default")
      (node (ref "CM2") (pin "146") (pinfunction "HDMI1_TX2_P_146") (pintype "output"))
    )
    (net (code "75") (name "unconnected-(J17-ID-Pad4)") (class "Default")
      (node (ref "J17") (pin "4") (pinfunction "ID_4") (pintype "passive"))
    )
    (net (code "76") (name "unconnected-(J19-Pad14)") (class "Default")
      (node (ref "J19") (pin "14") (pinfunction "14_14") (pintype "passive"))
    )
    (net (code "77") (name "unconnected-(U23-CRFILT-Pad14)") (class "Default")
      (node (ref "U23") (pin "14") (pinfunction "CRFILT_14") (pintype "passive"))
    )
    (net (code "78") (name "unconnected-(U23-PLLFILT-Pad34)") (class "Default")
      (node (ref "U23") (pin "34") (pinfunction "PLLFILT_34") (pintype "passive"))
    )
    (net (code "79") (name "unconnected-(U23-PRTPWR2{slash}BC_EN2-Pad16)") (class "Default")
      (node (ref "U23") (pin "16") (pinfunction "PRTPWR2/BC_EN2_16") (pintype "bidirectional"))
    )
    (net (code "80") (name "unconnected-(U23-PRTPWR3{slash}BC_EN3-Pad18)") (class "Default")
      (node (ref "U23") (pin "18") (pinfunction "PRTPWR3/BC_EN3_18") (pintype "bidirectional"))
    )
    (net (code "81") (name "unconnected-(U23-PRTPWR4{slash}BC_EN4-Pad20)") (class "Default")
      (node (ref "U23") (pin "20") (pinfunction "PRTPWR4/BC_EN4_20") (pintype "bidirectional"))
    )
    (net (code "82") (name "unconnected-(U23-TEST-Pad11)") (class "Default")
      (node (ref "U23") (pin "11") (pinfunction "TEST_11") (pintype "input+no_connect"))
    )
  )
)
